# Xduino8_0.net
KiCad netlist of a schematic drawn in EAGLE
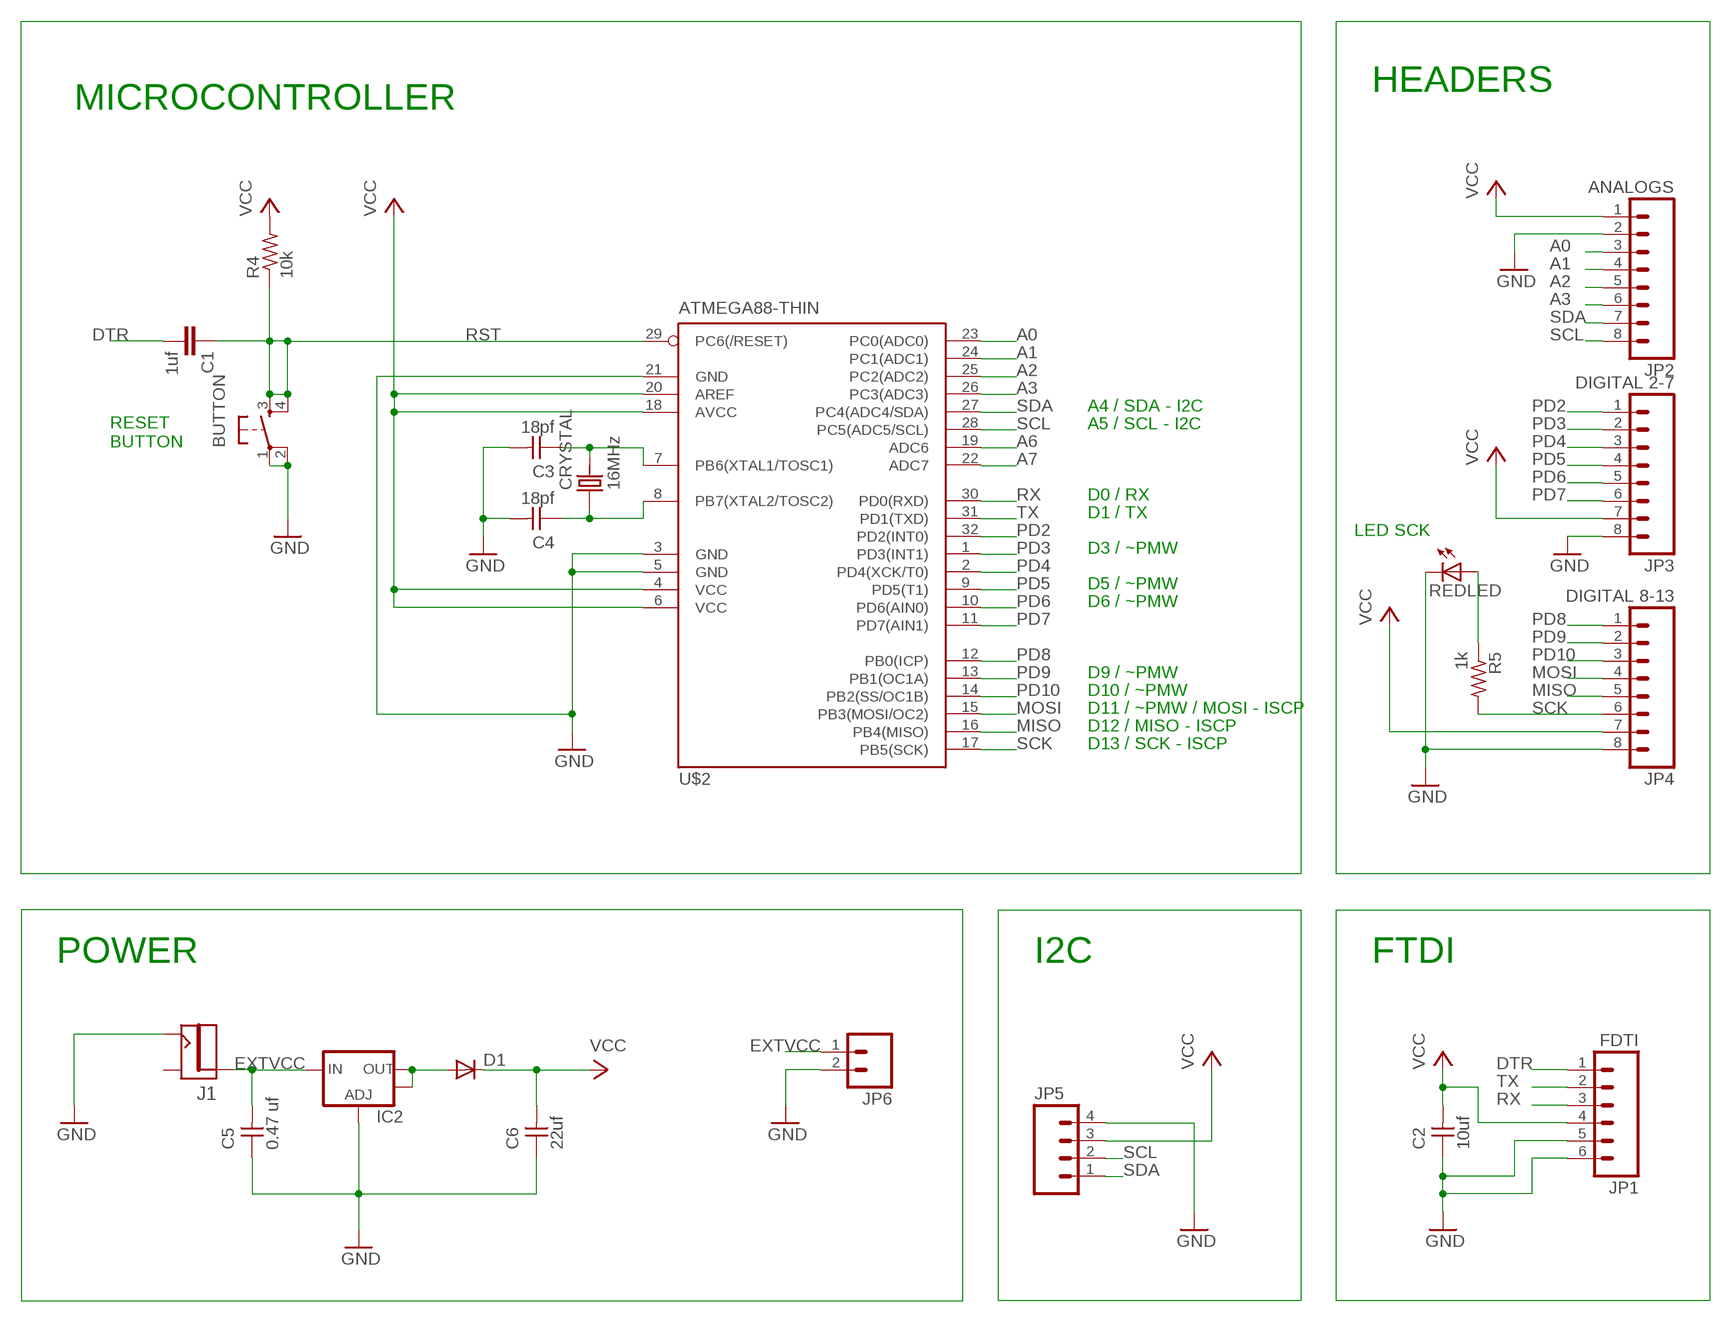
[diagram p0: schematic, sheet 1]

(export (version "E")
  (design (tool "Eeschema 10.0.6"))
  (components
    (comp (ref "BUTTON")
      (value "6MM_SWITCH6MM_SWITCH")
      (footprint "eagle-import:6MM_SWITCH")
      (libsource (lib "eagle-import") (part "6MM_SWITCH6MM_SWITCH"))
    )
    (comp (ref "C1")
      (value "1uf")
      (footprint "eagle-import:1206")
      (libsource (lib "eagle-import") (part "CAP1206"))
    )
    (comp (ref "C2")
      (value "10uf")
      (footprint "eagle-import:1206")
      (libsource (lib "eagle-import") (part "UNPOLARIZED_CAPACITOR1206"))
    )
    (comp (ref "C3")
      (value "18pf")
      (footprint "eagle-import:1206")
      (libsource (lib "eagle-import") (part "UNPOLARIZED_CAPACITOR1206"))
    )
    (comp (ref "C4")
      (value "18pf")
      (footprint "eagle-import:1206")
      (libsource (lib "eagle-import") (part "UNPOLARIZED_CAPACITOR1206"))
    )
    (comp (ref "C5")
      (value "0.47 uf")
      (footprint "eagle-import:1206")
      (libsource (lib "eagle-import") (part "UNPOLARIZED_CAPACITOR1206"))
    )
    (comp (ref "C6")
      (value "22uf")
      (footprint "eagle-import:1206")
      (libsource (lib "eagle-import") (part "UNPOLARIZED_CAPACITOR1206"))
    )
    (comp (ref "CRYSTAL")
      (value "16MHz")
      (footprint "eagle-import:CS10")
      (libsource (lib "eagle-import") (part "CRYSTALCS10"))
    )
    (comp (ref "D1")
      (value "DIODESOD123")
      (footprint "eagle-import:SOD123")
      (libsource (lib "eagle-import") (part "DIODESOD123"))
    )
    (comp (ref "IC2")
      (value "V_REG_LM1117SOT223")
      (footprint "eagle-import:SOT223")
      (libsource (lib "eagle-import") (part "V_REG_LM1117SOT223"))
    )
    (comp (ref "J1")
      (value "JACK.65MM")
      (footprint "eagle-import:JACK_.65MM")
      (libsource (lib "eagle-import") (part "JACK.65MM"))
    )
    (comp (ref "JP1")
      (value "FDTI")
      (footprint "eagle-import:1X06-SMD_EDGE")
      (libsource (lib "eagle-import") (part "M061X06-SMD_EDGE_FEMALE"))
    )
    (comp (ref "JP2")
      (value "ANALOGS")
      (footprint "eagle-import:1X08")
      (libsource (lib "eagle-import") (part "M08"))
    )
    (comp (ref "JP3")
      (value "DIGITAL 2-7")
      (footprint "eagle-import:1X08")
      (libsource (lib "eagle-import") (part "M08"))
    )
    (comp (ref "JP4")
      (value "DIGITAL 8-13")
      (footprint "eagle-import:1X08")
      (libsource (lib "eagle-import") (part "M08"))
    )
    (comp (ref "JP5")
      (value "M04PTH")
      (footprint "eagle-import:1X04")
      (libsource (lib "eagle-import") (part "M04PTH"))
    )
    (comp (ref "JP6")
      (value "M02PTH")
      (footprint "eagle-import:1X02")
      (libsource (lib "eagle-import") (part "M02PTH"))
    )
    (comp (ref "R4")
      (value "10k")
      (footprint "eagle-import:1206")
      (libsource (lib "eagle-import") (part "RESISTOR1206"))
    )
    (comp (ref "R5")
      (value "1k")
      (footprint "eagle-import:1206")
      (libsource (lib "eagle-import") (part "01_ng_RESISTOR1206"))
    )
    (comp (ref "REDLED")
      (value "LED1206")
      (footprint "eagle-import:1206")
      (libsource (lib "eagle-import") (part "LED1206"))
    )
    (comp (ref "U$2")
      (value "ATMEGA88-THIN")
      (footprint "eagle-import:TQFP32-08THIN")
      (libsource (lib "eagle-import") (part "ATMEGA88-THIN"))
    )
  )
  (nets
    (net (code "1") (name "/A0") (class "Default")
      (node (ref "JP2") (pin "3") (pinfunction "3_3") (pintype "passive"))
      (node (ref "U$2") (pin "23") (pinfunction "PC0(ADC0)_23") (pintype "bidirectional"))
    )
    (net (code "2") (name "/A1") (class "Default")
      (node (ref "JP2") (pin "4") (pinfunction "4_4") (pintype "passive"))
      (node (ref "U$2") (pin "24") (pinfunction "PC1(ADC1)_24") (pintype "bidirectional"))
    )
    (net (code "3") (name "/A2") (class "Default")
      (node (ref "JP2") (pin "5") (pinfunction "5_5") (pintype "passive"))
      (node (ref "U$2") (pin "25") (pinfunction "PC2(ADC2)_25") (pintype "bidirectional"))
    )
    (net (code "4") (name "/A3") (class "Default")
      (node (ref "JP2") (pin "6") (pinfunction "6_6") (pintype "passive"))
      (node (ref "U$2") (pin "26") (pinfunction "PC3(ADC3)_26") (pintype "bidirectional"))
    )
    (net (code "5") (name "/A6") (class "Default")
      (node (ref "U$2") (pin "19") (pinfunction "ADC6_19") (pintype "bidirectional"))
    )
    (net (code "6") (name "/A7") (class "Default")
      (node (ref "U$2") (pin "22") (pinfunction "ADC7_22") (pintype "bidirectional"))
    )
    (net (code "7") (name "/DTR") (class "Default")
      (node (ref "C1") (pin "2") (pinfunction "2_2") (pintype "passive"))
      (node (ref "JP1") (pin "1") (pinfunction "1_1") (pintype "passive"))
    )
    (net (code "8") (name "/EXTVCC") (class "Default")
      (node (ref "C5") (pin "2") (pinfunction "2_2") (pintype "passive"))
      (node (ref "IC2") (pin "3") (pinfunction "IN_3") (pintype "input"))
      (node (ref "J1") (pin "PIN") (pinfunction "PIN_PIN") (pintype "bidirectional"))
      (node (ref "JP6") (pin "1") (pinfunction "1_1") (pintype "passive"))
    )
    (net (code "9") (name "/MISO") (class "Default")
      (node (ref "JP4") (pin "5") (pinfunction "5_5") (pintype "passive"))
      (node (ref "U$2") (pin "16") (pinfunction "PB4(MISO)_16") (pintype "bidirectional"))
    )
    (net (code "10") (name "/MOSI") (class "Default")
      (node (ref "JP4") (pin "4") (pinfunction "4_4") (pintype "passive"))
      (node (ref "U$2") (pin "15") (pinfunction "PB3(MOSI/OC2)_15") (pintype "bidirectional"))
    )
    (net (code "11") (name "/PD2") (class "Default")
      (node (ref "JP3") (pin "1") (pinfunction "1_1") (pintype "passive"))
      (node (ref "U$2") (pin "32") (pinfunction "PD2(INT0)_32") (pintype "bidirectional"))
    )
    (net (code "12") (name "/PD3") (class "Default")
      (node (ref "JP3") (pin "2") (pinfunction "2_2") (pintype "passive"))
      (node (ref "U$2") (pin "1") (pinfunction "PD3(INT1)_1") (pintype "bidirectional"))
    )
    (net (code "13") (name "/PD4") (class "Default")
      (node (ref "JP3") (pin "3") (pinfunction "3_3") (pintype "passive"))
      (node (ref "U$2") (pin "2") (pinfunction "PD4(XCK/T0)_2") (pintype "bidirectional"))
    )
    (net (code "14") (name "/PD5") (class "Default")
      (node (ref "JP3") (pin "4") (pinfunction "4_4") (pintype "passive"))
      (node (ref "U$2") (pin "9") (pinfunction "PD5(T1)_9") (pintype "bidirectional"))
    )
    (net (code "15") (name "/PD6") (class "Default")
      (node (ref "JP3") (pin "5") (pinfunction "5_5") (pintype "passive"))
      (node (ref "U$2") (pin "10") (pinfunction "PD6(AIN0)_10") (pintype "bidirectional"))
    )
    (net (code "16") (name "/PD7") (class "Default")
      (node (ref "JP3") (pin "6") (pinfunction "6_6") (pintype "passive"))
      (node (ref "U$2") (pin "11") (pinfunction "PD7(AIN1)_11") (pintype "bidirectional"))
    )
    (net (code "17") (name "/PD8") (class "Default")
      (node (ref "JP4") (pin "1") (pinfunction "1_1") (pintype "passive"))
      (node (ref "U$2") (pin "12") (pinfunction "PB0(ICP)_12") (pintype "bidirectional"))
    )
    (net (code "18") (name "/PD9") (class "Default")
      (node (ref "JP4") (pin "2") (pinfunction "2_2") (pintype "passive"))
      (node (ref "U$2") (pin "13") (pinfunction "PB1(OC1A)_13") (pintype "bidirectional"))
    )
    (net (code "19") (name "/PD10") (class "Default")
      (node (ref "JP4") (pin "3") (pinfunction "3_3") (pintype "passive"))
      (node (ref "U$2") (pin "14") (pinfunction "PB2(SS/OC1B)_14") (pintype "bidirectional"))
    )
    (net (code "20") (name "/RST") (class "Default")
      (node (ref "BUTTON") (pin "3") (pinfunction "S_3") (pintype "passive"))
      (node (ref "BUTTON") (pin "4") (pinfunction "S1_4") (pintype "passive"))
      (node (ref "C1") (pin "1") (pinfunction "1_1") (pintype "passive"))
      (node (ref "R4") (pin "1") (pinfunction "1_1") (pintype "passive"))
      (node (ref "U$2") (pin "29") (pinfunction "PC6(/RESET)_29") (pintype "bidirectional"))
    )
    (net (code "21") (name "/RX") (class "Default")
      (node (ref "JP1") (pin "3") (pinfunction "3_3") (pintype "passive"))
      (node (ref "U$2") (pin "30") (pinfunction "PD0(RXD)_30") (pintype "bidirectional"))
    )
    (net (code "22") (name "/SCK") (class "Default")
      (node (ref "JP4") (pin "6") (pinfunction "6_6") (pintype "passive"))
      (node (ref "R5") (pin "2") (pinfunction "2_2") (pintype "passive"))
      (node (ref "U$2") (pin "17") (pinfunction "PB5(SCK)_17") (pintype "bidirectional"))
    )
    (net (code "23") (name "/SCL") (class "Default")
      (node (ref "JP2") (pin "8") (pinfunction "8_8") (pintype "passive"))
      (node (ref "JP5") (pin "2") (pinfunction "2_2") (pintype "passive"))
      (node (ref "U$2") (pin "28") (pinfunction "PC5(ADC5/SCL)_28") (pintype "bidirectional"))
    )
    (net (code "24") (name "/SDA") (class "Default")
      (node (ref "JP2") (pin "7") (pinfunction "7_7") (pintype "passive"))
      (node (ref "JP5") (pin "1") (pinfunction "1_1") (pintype "passive"))
      (node (ref "U$2") (pin "27") (pinfunction "PC4(ADC4/SDA)_27") (pintype "bidirectional"))
    )
    (net (code "25") (name "/TX") (class "Default")
      (node (ref "JP1") (pin "2") (pinfunction "2_2") (pintype "passive"))
      (node (ref "U$2") (pin "31") (pinfunction "PD1(TXD)_31") (pintype "bidirectional"))
    )
    (net (code "26") (name "GND") (class "Default")
      (node (ref "BUTTON") (pin "1") (pinfunction "P_1") (pintype "passive"))
      (node (ref "BUTTON") (pin "2") (pinfunction "P1_2") (pintype "passive"))
      (node (ref "C2") (pin "1") (pinfunction "1_1") (pintype "passive"))
      (node (ref "C3") (pin "2") (pinfunction "2_2") (pintype "passive"))
      (node (ref "C4") (pin "2") (pinfunction "2_2") (pintype "passive"))
      (node (ref "C5") (pin "1") (pinfunction "1_1") (pintype "passive"))
      (node (ref "C6") (pin "1") (pinfunction "1_1") (pintype "passive"))
      (node (ref "IC2") (pin "1") (pinfunction "ADJ_1") (pintype "input"))
      (node (ref "J1") (pin "SHUNT") (pinfunction "CONTACT_SHUNT") (pintype "bidirectional"))
      (node (ref "JP1") (pin "5") (pinfunction "5_5") (pintype "passive"))
      (node (ref "JP1") (pin "6") (pinfunction "6_6") (pintype "passive"))
      (node (ref "JP2") (pin "2") (pinfunction "2_2") (pintype "passive"))
      (node (ref "JP3") (pin "8") (pinfunction "8_8") (pintype "passive"))
      (node (ref "JP4") (pin "8") (pinfunction "8_8") (pintype "passive"))
      (node (ref "JP5") (pin "4") (pinfunction "4_4") (pintype "passive"))
      (node (ref "JP6") (pin "2") (pinfunction "2_2") (pintype "passive"))
      (node (ref "REDLED") (pin "2") (pinfunction "C_2") (pintype "passive"))
      (node (ref "U$2") (pin "21") (pinfunction "GND_21") (pintype "power_in"))
      (node (ref "U$2") (pin "3") (pinfunction "GND_3") (pintype "power_in"))
      (node (ref "U$2") (pin "5") (pinfunction "GND_5") (pintype "power_in"))
    )
    (net (code "27") (name "Net-(CRYSTAL-1)") (class "Default")
      (node (ref "C4") (pin "1") (pinfunction "1_1") (pintype "passive"))
      (node (ref "CRYSTAL") (pin "P$1") (pinfunction "1_P$1") (pintype "passive"))
      (node (ref "U$2") (pin "8") (pinfunction "PB7(XTAL2/TOSC2)_8") (pintype "bidirectional"))
    )
    (net (code "28") (name "Net-(CRYSTAL-2)") (class "Default")
      (node (ref "C3") (pin "1") (pinfunction "1_1") (pintype "passive"))
      (node (ref "CRYSTAL") (pin "P$2") (pinfunction "2_P$2") (pintype "passive"))
      (node (ref "U$2") (pin "7") (pinfunction "PB6(XTAL1/TOSC1)_7") (pintype "bidirectional"))
    )
    (net (code "29") (name "Net-(D1-A)") (class "Default")
      (node (ref "D1") (pin "ANODE") (pinfunction "A_ANODE") (pintype "passive"))
      (node (ref "IC2") (pin "2") (pinfunction "OUT_2") (pintype "output"))
      (node (ref "IC2") (pin "4") (pinfunction "OUT_4") (pintype "output"))
    )
    (net (code "30") (name "Net-(REDLED-A)") (class "Default")
      (node (ref "R5") (pin "1") (pinfunction "1_1") (pintype "passive"))
      (node (ref "REDLED") (pin "1") (pinfunction "A_1") (pintype "passive"))
    )
    (net (code "31") (name "VCC") (class "Default")
      (node (ref "C2") (pin "2") (pinfunction "2_2") (pintype "passive"))
      (node (ref "C6") (pin "2") (pinfunction "2_2") (pintype "passive"))
      (node (ref "D1") (pin "CATHODE") (pinfunction "C_CATHODE") (pintype "passive"))
      (node (ref "JP1") (pin "4") (pinfunction "4_4") (pintype "passive"))
      (node (ref "JP2") (pin "1") (pinfunction "1_1") (pintype "passive"))
      (node (ref "JP3") (pin "7") (pinfunction "7_7") (pintype "passive"))
      (node (ref "JP4") (pin "7") (pinfunction "7_7") (pintype "passive"))
      (node (ref "JP5") (pin "3") (pinfunction "3_3") (pintype "passive"))
      (node (ref "R4") (pin "2") (pinfunction "2_2") (pintype "passive"))
      (node (ref "U$2") (pin "18") (pinfunction "AVCC_18") (pintype "power_in"))
      (node (ref "U$2") (pin "20") (pinfunction "AREF_20") (pintype "passive"))
      (node (ref "U$2") (pin "4") (pinfunction "VCC_4") (pintype "power_in"))
      (node (ref "U$2") (pin "6") (pinfunction "VCC_6") (pintype "power_in"))
    )
    (net (code "32") (name "unconnected-(J1-SHUNT-PadCONTACT)") (class "Default")
      (node (ref "J1") (pin "CONTACT") (pinfunction "SHUNT_CONTACT") (pintype "bidirectional"))
    )
  )
)
